# SCH_04_MCU.net
KiCad netlist of a schematic drawn in Altium Designer
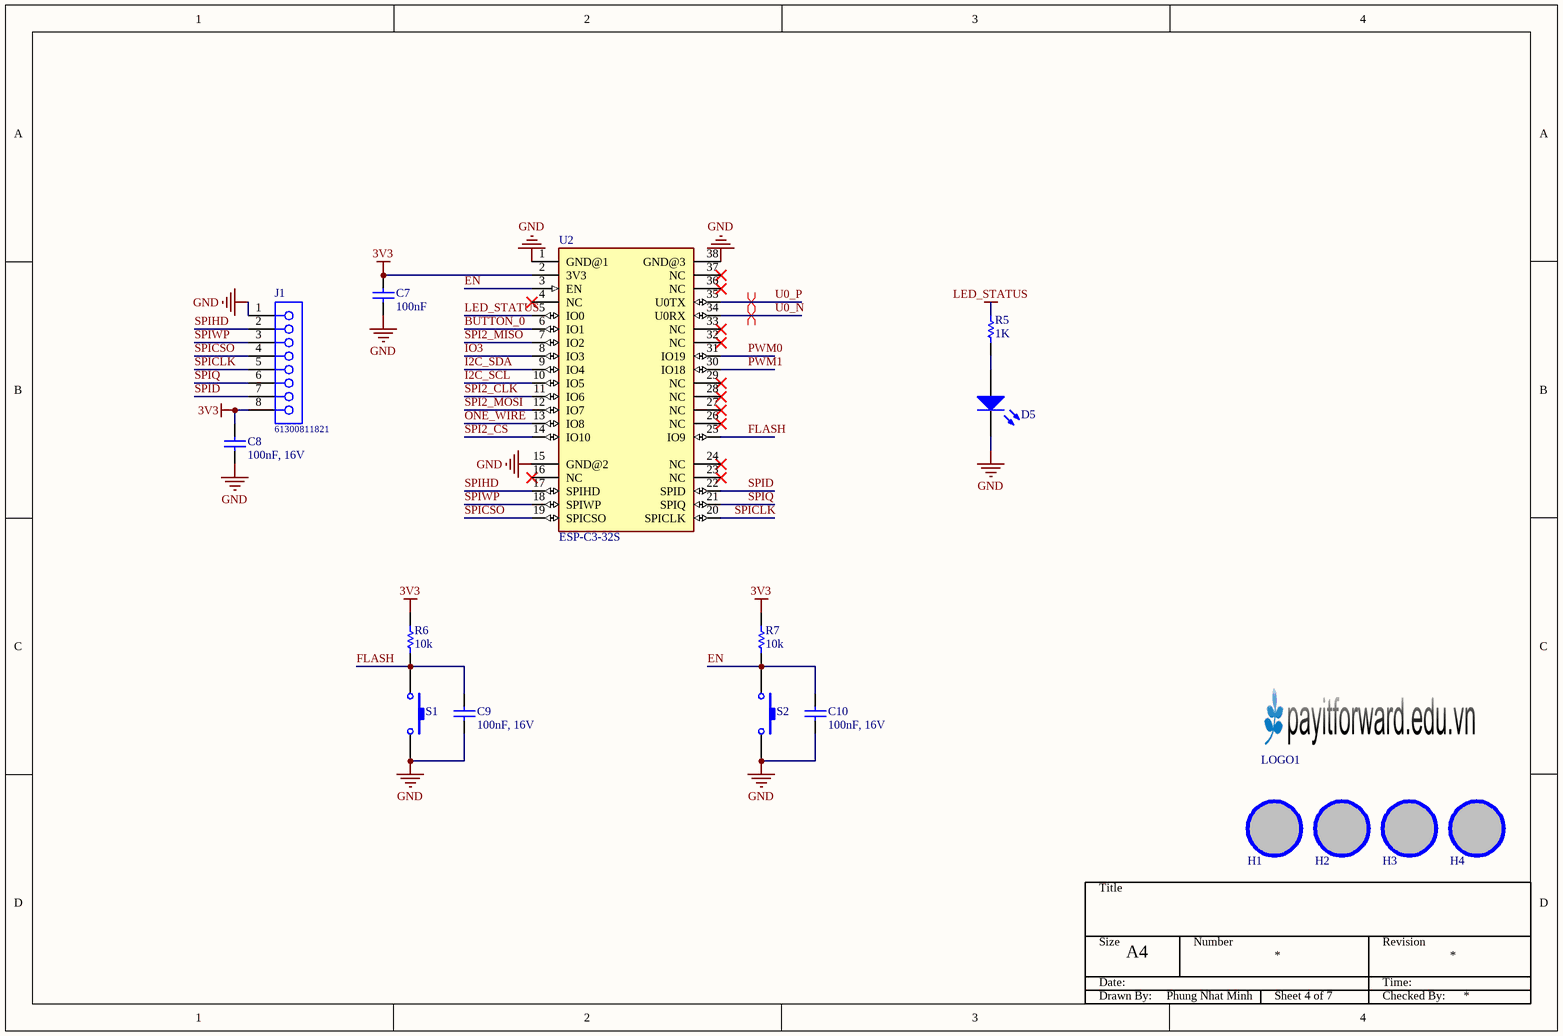
[diagram p0: SCH_04_MCU.SchDoc]

(export (version "E")
  (design (tool "Eeschema 10.0.6"))
  (components
    (comp (ref "C7")
      (value "100nF")
      (footprint "WCAP-CSGP_0603_H=0.8mm_Reflow")
      (description "WCAP-CSGP Multilayer Ceramic Chip Capacitor, General Purpose, size 0603, X7R, 100nF, 16V")
      (fields
        (field (name "MANUFACTURER PART NUMBER") "885012206046")
        (field (name "MANUFACTURER") "Wurth Elektronik")
      )
      (libsource (lib "Altium_WCAP-CSGP (rev20a)") (part "885012206046"))
    )
    (comp (ref "C8")
      (value "100nF, 16V")
      (footprint "WCAP-CSGP_0603_H=0.8mm_Reflow")
      (description "WCAP-CSGP Multilayer Ceramic Chip Capacitor, General Purpose, size 0603, X7R, 100nF, 16V")
      (fields
        (field (name "MANUFACTURER PART NUMBER") "885012206046")
        (field (name "MANUFACTURER") "Wurth Elektronik")
      )
      (libsource (lib "Altium_WCAP-CSGP (rev20a)") (part "885012206046"))
    )
    (comp (ref "C9")
      (value "100nF, 16V")
      (footprint "WCAP-CSGP_0603_H=0.8mm_Reflow")
      (description "WCAP-CSGP Multilayer Ceramic Chip Capacitor, General Purpose, size 0603, X7R, 100nF, 16V")
      (fields
        (field (name "MANUFACTURER PART NUMBER") "885012206046")
        (field (name "MANUFACTURER") "Wurth Elektronik")
      )
      (libsource (lib "Altium_WCAP-CSGP (rev20a)") (part "885012206046"))
    )
    (comp (ref "C10")
      (value "100nF, 16V")
      (footprint "WCAP-CSGP_0603_H=0.8mm_Reflow")
      (description "WCAP-CSGP Multilayer Ceramic Chip Capacitor, General Purpose, size 0603, X7R, 100nF, 16V")
      (fields
        (field (name "MANUFACTURER PART NUMBER") "885012206046")
        (field (name "MANUFACTURER") "Wurth Elektronik")
      )
      (libsource (lib "Altium_WCAP-CSGP (rev20a)") (part "885012206046"))
    )
    (comp (ref "D5")
      (value "LED SMD")
      (footprint "LED_0805_Blue")
      (description "LED")
      (libsource (lib "PIF_Library") (part "LED SMD"))
    )
    (comp (ref "H1")
      (value "Hole")
      (footprint "LO KHOAN 3MM")
      (description "Hole 3mm")
      (libsource (lib "PIF_Library") (part "Hole"))
    )
    (comp (ref "H2")
      (value "Hole")
      (footprint "LO KHOAN 3MM")
      (description "Hole 3mm")
      (libsource (lib "PIF_Library") (part "Hole"))
    )
    (comp (ref "H3")
      (value "Hole")
      (footprint "LO KHOAN 3MM")
      (description "Hole 3mm")
      (libsource (lib "PIF_Library") (part "Hole"))
    )
    (comp (ref "H4")
      (value "Hole")
      (footprint "LO KHOAN 3MM")
      (description "Hole 3mm")
      (libsource (lib "PIF_Library") (part "Hole"))
    )
    (comp (ref "J1")
      (value "61300811821")
      (footprint "61300811821")
      (description "WR-PHD Socket Header, THT, pitch 2.54mm, Single Row, Vertical, 8p")
      (fields (field (name "MANUFACTURER") "Wurth Elektronik"))
      (libsource (lib "Altium_WR-PHD (rev20a)") (part "61300811821"))
    )
    (comp (ref "LOGO1")
      (value "LOGO PIF")
      (footprint "PIF LOGO BIG SSTOP")
      (libsource (lib "PIF_Library") (part "LOGO PIF"))
    )
    (comp (ref "R5")
      (value "1K")
      (footprint "RES-SM-0603")
      (description "Resistor")
      (fields (field (name "Comment") "RESISTOR SMD"))
      (libsource (lib "PIF_Library") (part "RESISTOR SMD"))
    )
    (comp (ref "R6")
      (value "10k")
      (footprint "RES-SM-0603")
      (description "Resistor")
      (fields (field (name "Comment") "RESISTOR SMD"))
      (libsource (lib "PIF_Library") (part "RESISTOR SMD"))
    )
    (comp (ref "R7")
      (value "10k")
      (footprint "RES-SM-0603")
      (description "Resistor")
      (fields (field (name "Comment") "RESISTOR SMD"))
      (libsource (lib "PIF_Library") (part "RESISTOR SMD"))
    )
    (comp (ref "S1")
      (value "Tact SW - 2Pin")
      (footprint "SW-SMD")
      (description "Switch button 2 pin")
      (libsource (lib "PIF_Library") (part "Tact SW - 2Pin"))
    )
    (comp (ref "S2")
      (value "Tact SW - 2Pin")
      (footprint "SW-SMD")
      (description "Switch button 2 pin")
      (libsource (lib "PIF_Library") (part "Tact SW - 2Pin"))
    )
    (comp (ref "U2")
      (value "ESP-C3-32S")
      (footprint "ESP-32S")
      (description "- - Transceiver Module - - Surface Mount")
      (fields (field (name "MP") "ESP-32S") (field (name "MF") "Olimex LTD"))
      (libsource (lib "ESP-C3-32S") (part "ESP-C3-32S"))
    )
  )
  (nets
    (net (code "1") (name "/BUTTON_0") (class "Default")
      (node (ref "U2") (pin "6") (pinfunction "IO1_6") (pintype "bidirectional"))
    )
    (net (code "2") (name "/EN") (class "Default")
      (node (ref "C10") (pin "2") (pinfunction "2_2") (pintype "passive"))
      (node (ref "R7") (pin "2") (pinfunction "2_2") (pintype "passive"))
      (node (ref "S2") (pin "1") (pinfunction "1_1") (pintype "passive"))
      (node (ref "U2") (pin "3") (pinfunction "EN_3") (pintype "input"))
    )
    (net (code "3") (name "/FLASH") (class "Default")
      (node (ref "C9") (pin "2") (pinfunction "2_2") (pintype "passive"))
      (node (ref "R6") (pin "2") (pinfunction "2_2") (pintype "passive"))
      (node (ref "S1") (pin "1") (pinfunction "1_1") (pintype "passive"))
      (node (ref "U2") (pin "25") (pinfunction "IO9_25") (pintype "bidirectional"))
    )
    (net (code "4") (name "/I2C_SCL") (class "Default")
      (node (ref "U2") (pin "10") (pinfunction "IO5_10") (pintype "bidirectional"))
    )
    (net (code "5") (name "/I2C_SDA") (class "Default")
      (node (ref "U2") (pin "9") (pinfunction "IO4_9") (pintype "bidirectional"))
    )
    (net (code "6") (name "/IO3") (class "Default")
      (node (ref "U2") (pin "8") (pinfunction "IO3_8") (pintype "bidirectional"))
    )
    (net (code "7") (name "/ONE_WIRE") (class "Default")
      (node (ref "U2") (pin "13") (pinfunction "IO8_13") (pintype "bidirectional"))
    )
    (net (code "8") (name "/PWM0") (class "Default")
      (node (ref "U2") (pin "31") (pinfunction "IO19_31") (pintype "bidirectional"))
    )
    (net (code "9") (name "/PWM1") (class "Default")
      (node (ref "U2") (pin "30") (pinfunction "IO18_30") (pintype "bidirectional"))
    )
    (net (code "10") (name "/SPI2_CLK") (class "Default")
      (node (ref "U2") (pin "11") (pinfunction "IO6_11") (pintype "bidirectional"))
    )
    (net (code "11") (name "/SPI2_CS") (class "Default")
      (node (ref "U2") (pin "14") (pinfunction "IO10_14") (pintype "bidirectional"))
    )
    (net (code "12") (name "/SPI2_MISO") (class "Default")
      (node (ref "U2") (pin "7") (pinfunction "IO2_7") (pintype "bidirectional"))
    )
    (net (code "13") (name "/SPI2_MOSI") (class "Default")
      (node (ref "U2") (pin "12") (pinfunction "IO7_12") (pintype "bidirectional"))
    )
    (net (code "14") (name "/SPICLK") (class "Default")
      (node (ref "J1") (pin "5") (pinfunction "5_5") (pintype "passive"))
      (node (ref "U2") (pin "20") (pinfunction "SPICLK_20") (pintype "bidirectional"))
    )
    (net (code "15") (name "/SPICSO") (class "Default")
      (node (ref "J1") (pin "4") (pinfunction "4_4") (pintype "passive"))
      (node (ref "U2") (pin "19") (pinfunction "SPICSO_19") (pintype "bidirectional"))
    )
    (net (code "16") (name "/SPID") (class "Default")
      (node (ref "J1") (pin "7") (pinfunction "7_7") (pintype "passive"))
      (node (ref "U2") (pin "22") (pinfunction "SPID_22") (pintype "bidirectional"))
    )
    (net (code "17") (name "/SPIHD") (class "Default")
      (node (ref "J1") (pin "2") (pinfunction "2_2") (pintype "passive"))
      (node (ref "U2") (pin "17") (pinfunction "SPIHD_17") (pintype "bidirectional"))
    )
    (net (code "18") (name "/SPIQ") (class "Default")
      (node (ref "J1") (pin "6") (pinfunction "6_6") (pintype "passive"))
      (node (ref "U2") (pin "21") (pinfunction "SPIQ_21") (pintype "bidirectional"))
    )
    (net (code "19") (name "/SPIWP") (class "Default")
      (node (ref "J1") (pin "3") (pinfunction "3_3") (pintype "passive"))
      (node (ref "U2") (pin "18") (pinfunction "SPIWP_18") (pintype "bidirectional"))
    )
    (net (code "20") (name "/U0_N") (class "Default")
      (node (ref "U2") (pin "34") (pinfunction "U0RX_34") (pintype "bidirectional"))
    )
    (net (code "21") (name "/U0_P") (class "Default")
      (node (ref "U2") (pin "35") (pinfunction "U0TX_35") (pintype "bidirectional"))
    )
    (net (code "22") (name "3V3") (class "Default")
      (node (ref "C7") (pin "2") (pinfunction "2_2") (pintype "passive"))
      (node (ref "C8") (pin "2") (pinfunction "2_2") (pintype "passive"))
      (node (ref "J1") (pin "8") (pinfunction "8_8") (pintype "passive"))
      (node (ref "R6") (pin "1") (pinfunction "1_1") (pintype "passive"))
      (node (ref "R7") (pin "1") (pinfunction "1_1") (pintype "passive"))
      (node (ref "U2") (pin "2") (pinfunction "3V3_2") (pintype "power_in"))
    )
    (net (code "23") (name "GND") (class "Default")
      (node (ref "C10") (pin "1") (pinfunction "1_1") (pintype "passive"))
      (node (ref "C7") (pin "1") (pinfunction "1_1") (pintype "passive"))
      (node (ref "C8") (pin "1") (pinfunction "1_1") (pintype "passive"))
      (node (ref "C9") (pin "1") (pinfunction "1_1") (pintype "passive"))
      (node (ref "D5") (pin "2") (pinfunction "K_2") (pintype "passive"))
      (node (ref "J1") (pin "1") (pinfunction "1_1") (pintype "passive"))
      (node (ref "S1") (pin "2") (pinfunction "2_2") (pintype "passive"))
      (node (ref "S2") (pin "2") (pinfunction "2_2") (pintype "passive"))
      (node (ref "U2") (pin "1") (pinfunction "GND@1_1") (pintype "power_in"))
      (node (ref "U2") (pin "15") (pinfunction "GND@2_15") (pintype "power_in"))
      (node (ref "U2") (pin "38") (pinfunction "GND@3_38") (pintype "power_in"))
    )
    (net (code "24") (name "LED_STATUS") (class "Default")
      (node (ref "R5") (pin "2") (pinfunction "2_2") (pintype "passive"))
      (node (ref "U2") (pin "5") (pinfunction "IO0_5") (pintype "bidirectional"))
    )
    (net (code "25") (name "Net-(D5-A)") (class "Default")
      (node (ref "D5") (pin "1") (pinfunction "A_1") (pintype "passive"))
      (node (ref "R5") (pin "1") (pinfunction "1_1") (pintype "passive"))
    )
    (net (code "26") (name "unconnected-(H1-Pad1)") (class "Default")
      (node (ref "H1") (pin "1") (pinfunction "1_1") (pintype "passive"))
    )
    (net (code "27") (name "unconnected-(H2-Pad1)") (class "Default")
      (node (ref "H2") (pin "1") (pinfunction "1_1") (pintype "passive"))
    )
    (net (code "28") (name "unconnected-(H3-Pad1)") (class "Default")
      (node (ref "H3") (pin "1") (pinfunction "1_1") (pintype "passive"))
    )
    (net (code "29") (name "unconnected-(H4-Pad1)") (class "Default")
      (node (ref "H4") (pin "1") (pinfunction "1_1") (pintype "passive"))
    )
    (net (code "30") (name "unconnected-(U2-NC-Pad4)") (class "Default")
      (node (ref "U2") (pin "4") (pinfunction "NC_4") (pintype "power_in+no_connect"))
    )
    (net (code "31") (name "unconnected-(U2-NC-Pad16)") (class "Default")
      (node (ref "U2") (pin "16") (pinfunction "NC_16") (pintype "power_in+no_connect"))
    )
    (net (code "32") (name "unconnected-(U2-NC-Pad23)") (class "Default")
      (node (ref "U2") (pin "23") (pinfunction "NC_23") (pintype "power_in+no_connect"))
    )
    (net (code "33") (name "unconnected-(U2-NC-Pad24)") (class "Default")
      (node (ref "U2") (pin "24") (pinfunction "NC_24") (pintype "power_in+no_connect"))
    )
    (net (code "34") (name "unconnected-(U2-NC-Pad26)") (class "Default")
      (node (ref "U2") (pin "26") (pinfunction "NC_26") (pintype "power_in+no_connect"))
    )
    (net (code "35") (name "unconnected-(U2-NC-Pad27)") (class "Default")
      (node (ref "U2") (pin "27") (pinfunction "NC_27") (pintype "power_in+no_connect"))
    )
    (net (code "36") (name "unconnected-(U2-NC-Pad28)") (class "Default")
      (node (ref "U2") (pin "28") (pinfunction "NC_28") (pintype "power_in+no_connect"))
    )
    (net (code "37") (name "unconnected-(U2-NC-Pad29)") (class "Default")
      (node (ref "U2") (pin "29") (pinfunction "NC_29") (pintype "power_in+no_connect"))
    )
    (net (code "38") (name "unconnected-(U2-NC-Pad32)") (class "Default")
      (node (ref "U2") (pin "32") (pinfunction "NC_32") (pintype "power_in+no_connect"))
    )
    (net (code "39") (name "unconnected-(U2-NC-Pad33)") (class "Default")
      (node (ref "U2") (pin "33") (pinfunction "NC_33") (pintype "power_in+no_connect"))
    )
    (net (code "40") (name "unconnected-(U2-NC-Pad36)") (class "Default")
      (node (ref "U2") (pin "36") (pinfunction "NC_36") (pintype "power_in+no_connect"))
    )
    (net (code "41") (name "unconnected-(U2-NC-Pad37)") (class "Default")
      (node (ref "U2") (pin "37") (pinfunction "NC_37") (pintype "power_in+no_connect"))
    )
  )
)
